# TOP.net
KiCad netlist of a schematic drawn in Altium Designer
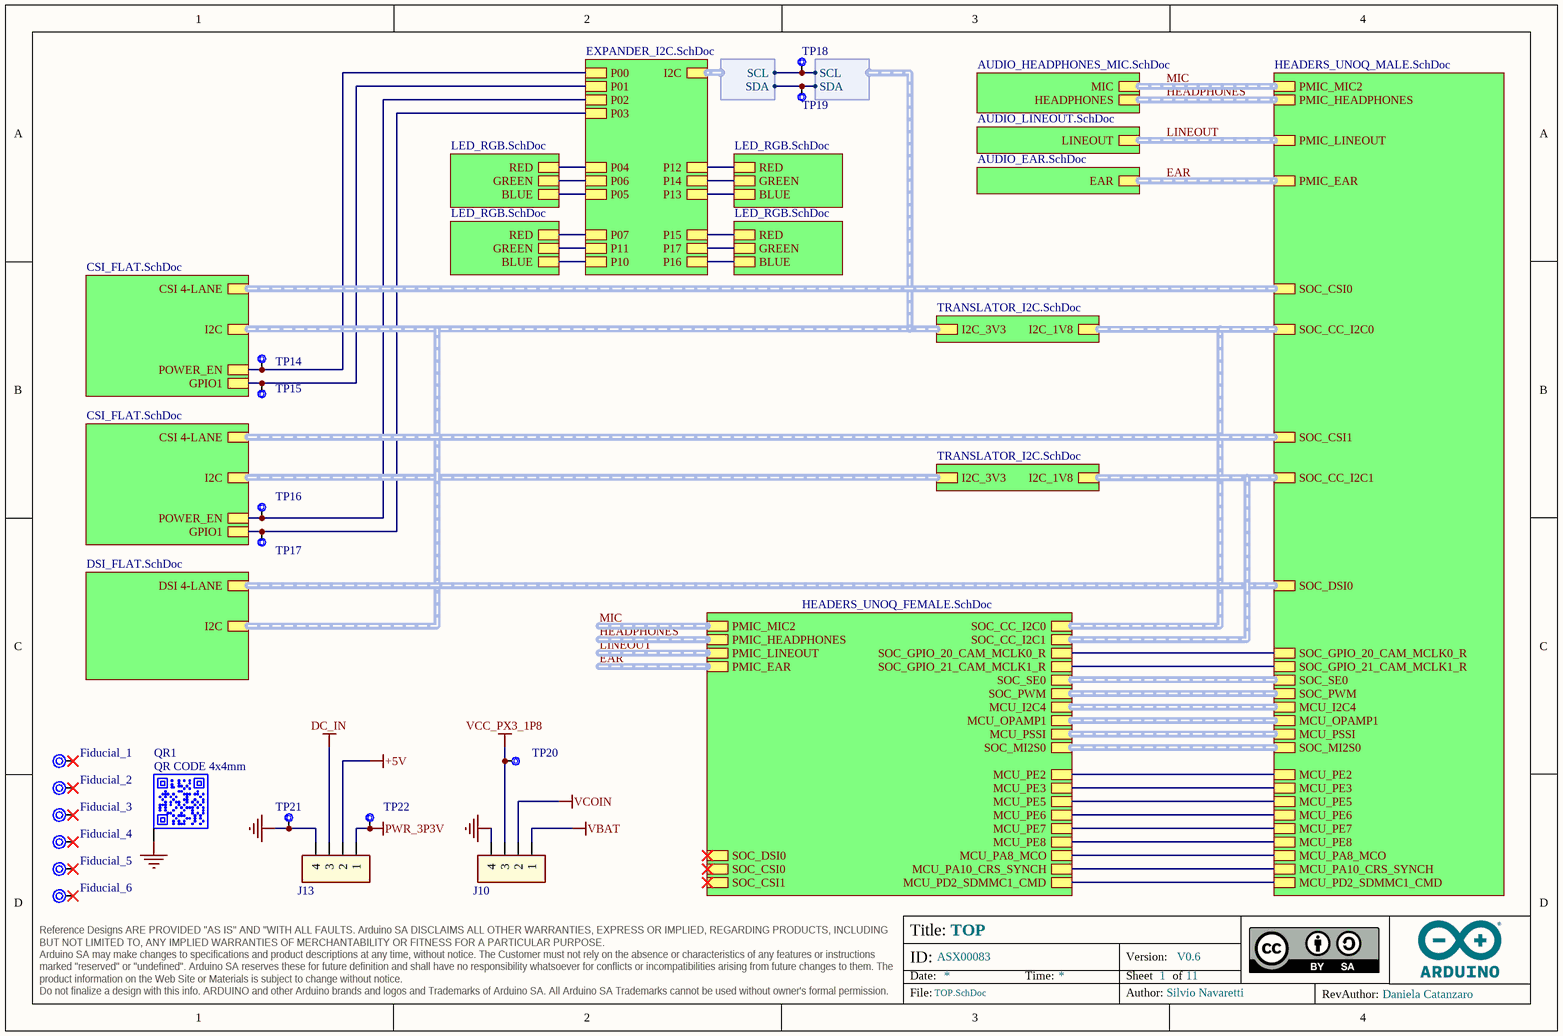
[diagram p0: TOP.SchDoc]

(export (version "E")
  (design (tool "Eeschema 10.0.6"))
  (components
    (comp (ref "Fiducial_1")
      (value "Fiducial mark 1mm with 2mm solder")
      (footprint "Fiducial mark 1mm with circle-Footprint-1")
      (libsource (lib "Clean") (part "Fiducial mark 1mm with circle"))
    )
    (comp (ref "Fiducial_2")
      (value "Fiducial mark 1mm with 2mm solder")
      (footprint "Fiducial mark 1mm with circle-Footprint-1")
      (libsource (lib "Clean") (part "Fiducial mark 1mm with circle"))
    )
    (comp (ref "Fiducial_3")
      (value "Fiducial mark 1mm with 2mm solder")
      (footprint "Fiducial mark 1mm with circle-Footprint-1")
      (libsource (lib "Clean") (part "Fiducial mark 1mm with circle"))
    )
    (comp (ref "Fiducial_4")
      (value "Fiducial mark 1mm with 2mm solder")
      (footprint "Fiducial mark 1mm with circle-Footprint-1")
      (libsource (lib "Clean") (part "Fiducial mark 1mm with circle"))
    )
    (comp (ref "Fiducial_5")
      (value "Fiducial mark 1mm with 2mm solder")
      (footprint "Fiducial mark 1mm with circle-Footprint-1")
      (libsource (lib "Clean") (part "Fiducial mark 1mm with circle"))
    )
    (comp (ref "Fiducial_6")
      (value "Fiducial mark 1mm with 2mm solder")
      (footprint "Fiducial mark 1mm with circle-Footprint-1")
      (libsource (lib "Clean") (part "Fiducial mark 1mm with circle"))
    )
    (comp (ref "J10")
      (value "HEADER TH 2.54mm VERT. 1x004POS")
      (footprint "PIN HEADER 2.54mm VERT. 1x4POS-Footprint-1")
      (libsource (lib "Clean") (part "PIN HEADER 2.54mm VERT. 1x4POS"))
    )
    (comp (ref "J13")
      (value "HEADER TH 2.54mm VERT. 1x004POS")
      (footprint "PIN HEADER 2.54mm VERT. 1x4POS-Footprint-1")
      (libsource (lib "Clean") (part "PIN HEADER 2.54mm VERT. 1x4POS"))
    )
    (comp (ref "QR1")
      (value "QR CODE 4x4mm")
      (footprint "QR CODE 4x4mm")
      (description "QR CODE 4x4mm on layer 34 (This is not a component)")
      (fields (field (name "PART NUMBER") "This is not a component"))
      (libsource (lib "Clean") (part "QR CODE 4x4mm"))
    )
    (comp (ref "TP14")
      (value "Test point 1.00mm")
      (footprint "TP-1.00MM")
      (fields (field (name "MANUFACTURER") "This is not a component"))
      (libsource (lib "Clean") (part "TESTPOINT"))
    )
    (comp (ref "TP15")
      (value "Test point 1.00mm")
      (footprint "TP-1.00MM")
      (fields (field (name "MANUFACTURER") "This is not a component"))
      (libsource (lib "Clean") (part "TESTPOINT"))
    )
    (comp (ref "TP16")
      (value "Test point 1.00mm")
      (footprint "TP-1.00MM")
      (fields (field (name "MANUFACTURER") "This is not a component"))
      (libsource (lib "Clean") (part "TESTPOINT"))
    )
    (comp (ref "TP17")
      (value "Test point 1.00mm")
      (footprint "TP-1.00MM")
      (fields (field (name "MANUFACTURER") "This is not a component"))
      (libsource (lib "Clean") (part "TESTPOINT"))
    )
    (comp (ref "TP18")
      (value "Test point 1.00mm")
      (footprint "TP-1.00MM")
      (fields (field (name "MANUFACTURER") "This is not a component"))
      (libsource (lib "Clean") (part "TESTPOINT"))
    )
    (comp (ref "TP19")
      (value "Test point 1.00mm")
      (footprint "TP-1.00MM")
      (fields (field (name "MANUFACTURER") "This is not a component"))
      (libsource (lib "Clean") (part "TESTPOINT"))
    )
    (comp (ref "TP20")
      (value "Test point 1.00mm")
      (footprint "TP-1.00MM")
      (fields (field (name "MANUFACTURER") "This is not a component"))
      (libsource (lib "Clean") (part "TESTPOINT"))
    )
    (comp (ref "TP21")
      (value "Test point 1.00mm")
      (footprint "TP-1.00MM")
      (fields (field (name "MANUFACTURER") "This is not a component"))
      (libsource (lib "Clean") (part "TESTPOINT"))
    )
    (comp (ref "TP22")
      (value "Test point 1.00mm")
      (footprint "TP-1.00MM")
      (fields (field (name "MANUFACTURER") "This is not a component"))
      (libsource (lib "Clean") (part "TESTPOINT"))
    )
  )
  (nets
    (net (code "6") (name "+5V") (class "Default")
      (node (ref "J13") (pin "2") (pinfunction "2_2") (pintype "passive"))
    )
    (net (code "14") (name "/GPIO1") (class "Default")
      (node (ref "TP17") (pin "X") (pinfunction "X_X") (pintype "passive"))
    )
    (net (code "15") (name "/GPIO1_1") (class "Default")
      (node (ref "TP15") (pin "X") (pinfunction "X_X") (pintype "passive"))
    )
    (net (code "35") (name "/P00") (class "Default")
      (node (ref "TP14") (pin "X") (pinfunction "X_X") (pintype "passive"))
    )
    (net (code "36") (name "/P02") (class "Default")
      (node (ref "TP16") (pin "X") (pinfunction "X_X") (pintype "passive"))
    )
    (net (code "54") (name "DC_IN") (class "Default")
      (node (ref "J13") (pin "3") (pinfunction "3_3") (pintype "passive"))
    )
    (net (code "55") (name "GND") (class "Default")
      (node (ref "J10") (pin "4") (pinfunction "4_4") (pintype "passive"))
      (node (ref "J13") (pin "4") (pinfunction "4_4") (pintype "passive"))
      (node (ref "QR1") (pin "PAD") (pinfunction "PAD_PAD") (pintype "passive"))
      (node (ref "TP21") (pin "X") (pinfunction "X_X") (pintype "passive"))
    )
    (net (code "56") (name "PWR_3P3V") (class "Default")
      (node (ref "J13") (pin "1") (pinfunction "1_1") (pintype "passive"))
      (node (ref "TP22") (pin "X") (pinfunction "X_X") (pintype "passive"))
    )
    (net (code "57") (name "VBAT") (class "Default")
      (node (ref "J10") (pin "1") (pinfunction "1_1") (pintype "passive"))
    )
    (net (code "58") (name "VCC_PX3_1P8") (class "Default")
      (node (ref "J10") (pin "3") (pinfunction "3_3") (pintype "passive"))
      (node (ref "TP20") (pin "X") (pinfunction "X_X") (pintype "passive"))
    )
    (net (code "59") (name "VCOIN") (class "Default")
      (node (ref "J10") (pin "2") (pinfunction "2_2") (pintype "passive"))
    )
    (net (code "60") (name "unconnected-(Fiducial_1-Pad1)") (class "Default")
      (node (ref "Fiducial_1") (pin "1") (pinfunction "1_1") (pintype "passive+no_connect"))
    )
    (net (code "61") (name "unconnected-(Fiducial_2-Pad1)") (class "Default")
      (node (ref "Fiducial_2") (pin "1") (pinfunction "1_1") (pintype "passive+no_connect"))
    )
    (net (code "62") (name "unconnected-(Fiducial_3-Pad1)") (class "Default")
      (node (ref "Fiducial_3") (pin "1") (pinfunction "1_1") (pintype "passive+no_connect"))
    )
    (net (code "63") (name "unconnected-(Fiducial_4-Pad1)") (class "Default")
      (node (ref "Fiducial_4") (pin "1") (pinfunction "1_1") (pintype "passive+no_connect"))
    )
    (net (code "64") (name "unconnected-(Fiducial_5-Pad1)") (class "Default")
      (node (ref "Fiducial_5") (pin "1") (pinfunction "1_1") (pintype "passive+no_connect"))
    )
    (net (code "65") (name "unconnected-(Fiducial_6-Pad1)") (class "Default")
      (node (ref "Fiducial_6") (pin "1") (pinfunction "1_1") (pintype "passive+no_connect"))
    )
    (net (code "66") (name "unconnected-(TP18-PadX)") (class "Default")
      (node (ref "TP18") (pin "X") (pinfunction "X_X") (pintype "passive"))
    )
    (net (code "67") (name "unconnected-(TP19-PadX)") (class "Default")
      (node (ref "TP19") (pin "X") (pinfunction "X_X") (pintype "passive"))
    )
  )
)
